# Fake6509_v2.net
KiCad netlist of a schematic drawn in EAGLE
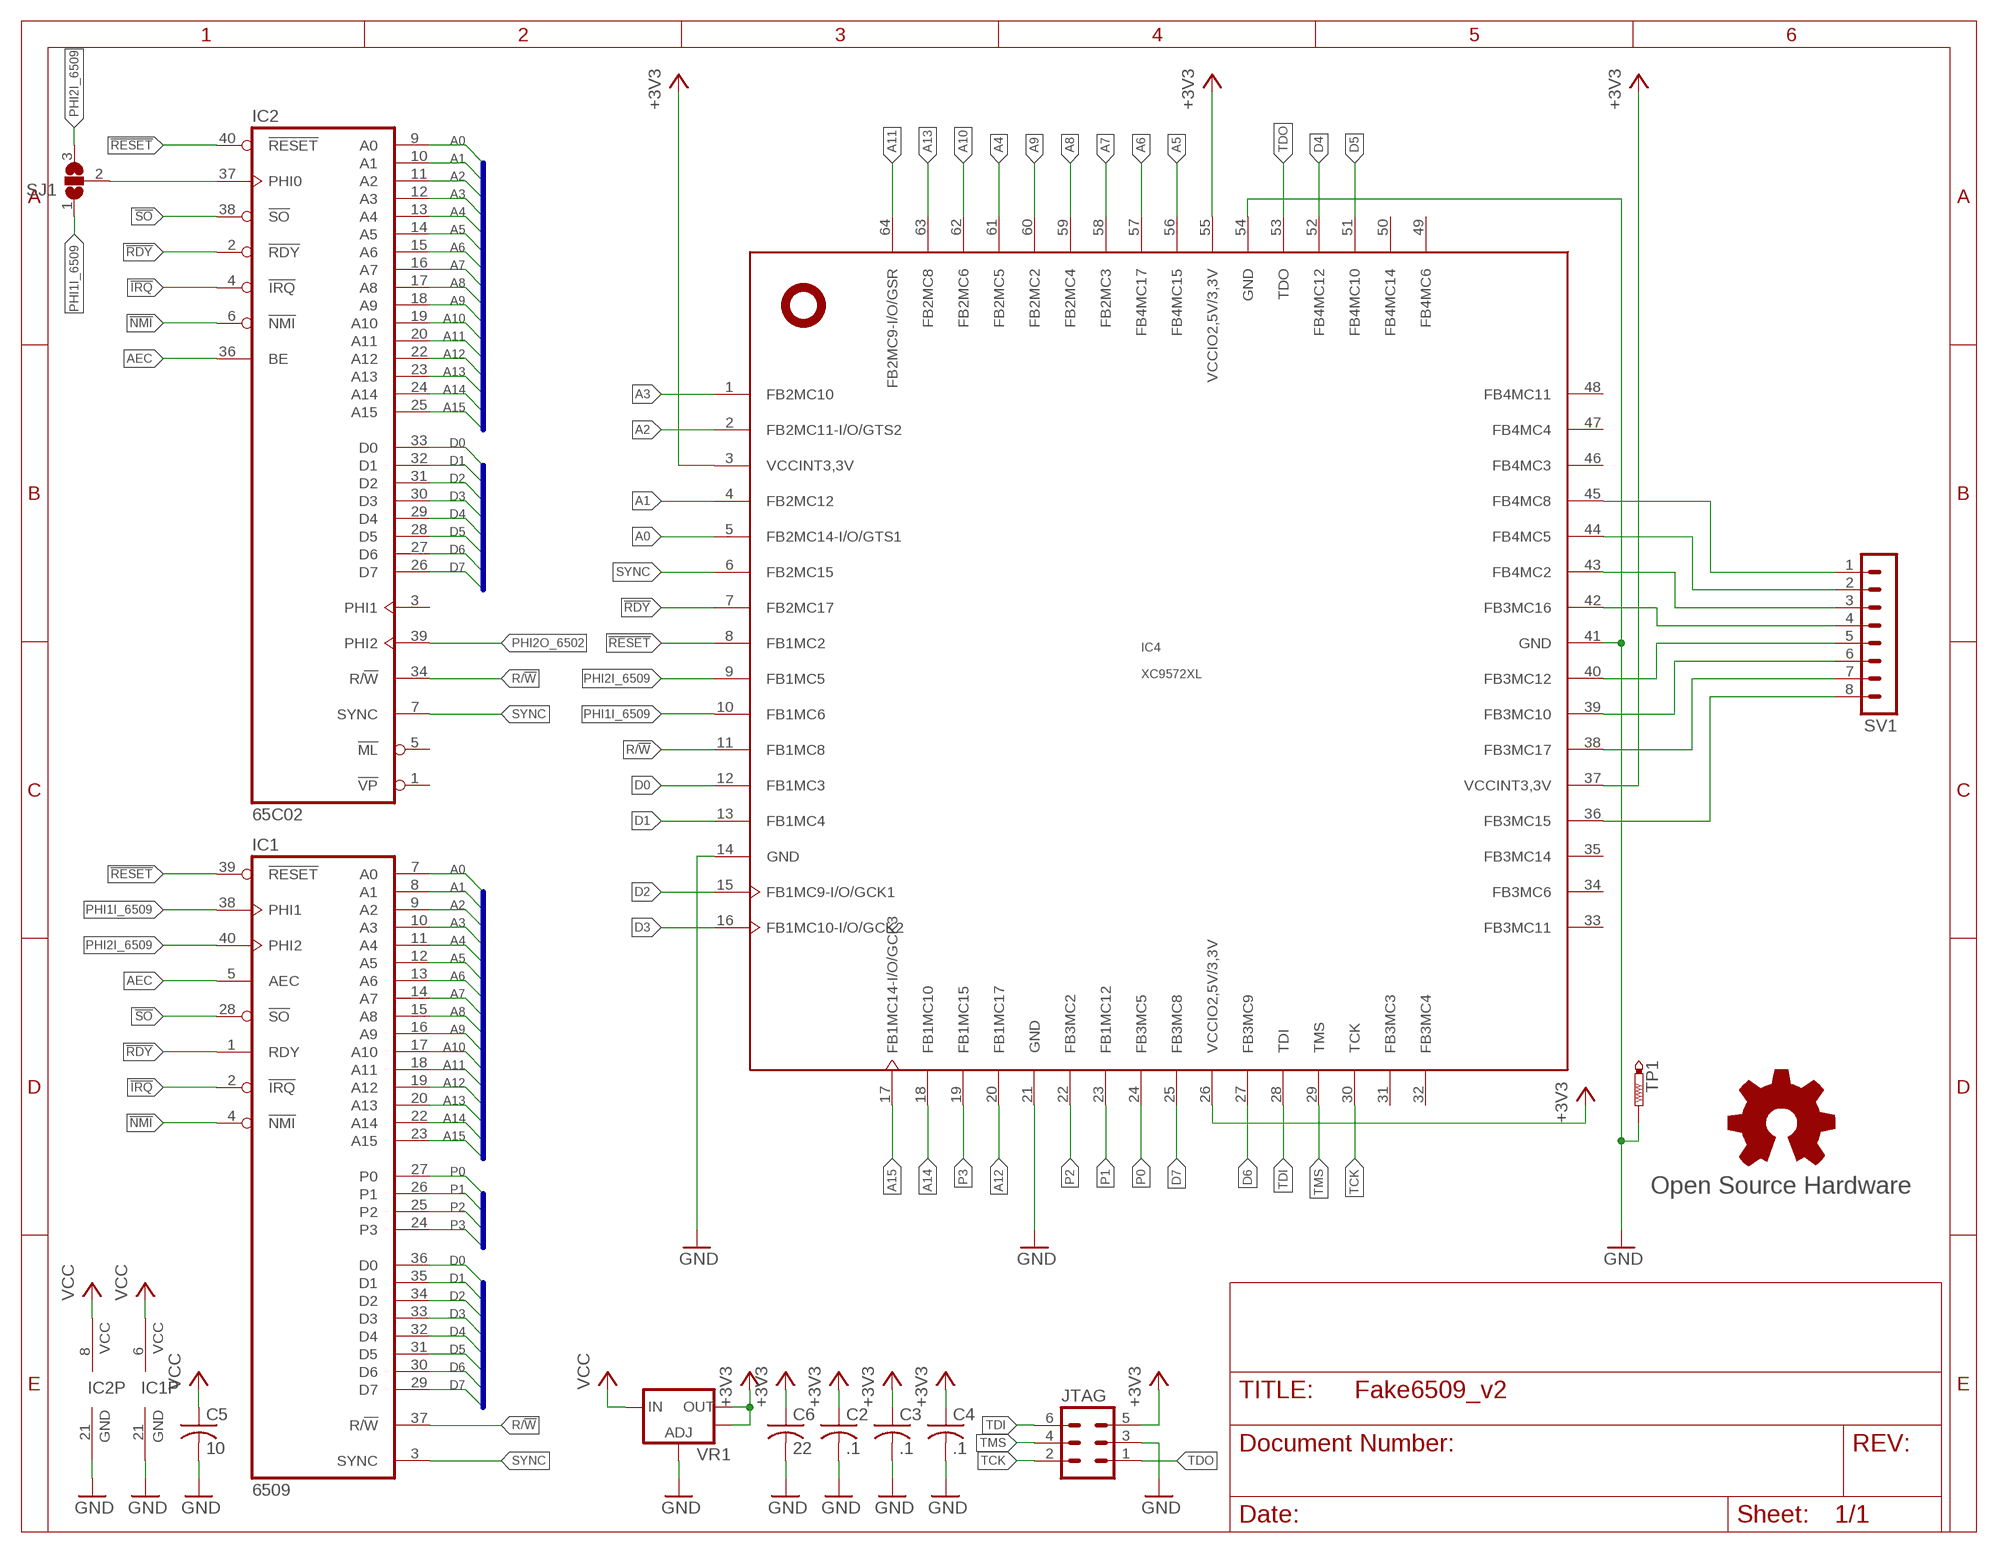
[diagram p0: schematic, sheet 1]

(export (version "E")
  (design (tool "Eeschema 10.0.6"))
  (components
    (comp (ref "C2")
      (value ".1")
      (footprint "eagle-import:C0402")
      (libsource (lib "eagle-import") (part "C-USC0402"))
    )
    (comp (ref "C3")
      (value ".1")
      (footprint "eagle-import:C0402")
      (libsource (lib "eagle-import") (part "C-USC0402"))
    )
    (comp (ref "C4")
      (value ".1")
      (footprint "eagle-import:C0402")
      (libsource (lib "eagle-import") (part "C-USC0402"))
    )
    (comp (ref "C5")
      (value "10")
      (footprint "eagle-import:C0805")
      (libsource (lib "eagle-import") (part "C-USC0805"))
    )
    (comp (ref "C6")
      (value "22")
      (footprint "eagle-import:C0805")
      (libsource (lib "eagle-import") (part "C-USC0805"))
    )
    (comp (ref "GOLD_ORB_SM1")
      (value "Open Source Hardware")
      (footprint "eagle-import:OSHW_5MM")
      (libsource (lib "eagle-import") (part "OSHWLOGOLOGO5MM"))
    )
    (comp (ref "IC1")
      (value "6509")
      (footprint "eagle-import:DIL40-ROUNDPAD")
      (libsource (lib "eagle-import") (part "6509-RP"))
    )
    (comp (ref "IC2")
      (value "65C02")
      (footprint "eagle-import:DIL40-ROUNDPAD")
      (libsource (lib "eagle-import") (part "W65C02SP-R"))
    )
    (comp (ref "IC4")
      (value "XC9572XL")
      (footprint "eagle-import:VQFP64")
      (libsource (lib "eagle-import") (part "XC9572XLVQG64"))
    )
    (comp (ref "JTAG")
      (value "MA03-2")
      (footprint "eagle-import:MA03-2")
      (libsource (lib "eagle-import") (part "MA03-2"))
    )
    (comp (ref "SJ1")
      (value "SJ2W")
      (footprint "eagle-import:SJ_2")
      (libsource (lib "eagle-import") (part "SJ2W"))
    )
    (comp (ref "SV1")
      (value "MA08-1")
      (footprint "eagle-import:MA08-1")
      (libsource (lib "eagle-import") (part "MA08-1"))
    )
    (comp (ref "TP1")
      (value "PTR1B1,27")
      (footprint "eagle-import:B1,27")
      (libsource (lib "eagle-import") (part "PTR1B1,27"))
    )
    (comp (ref "VR1")
      (value "V_REG_LM1117SOT223")
      (footprint "eagle-import:SOT223")
      (libsource (lib "eagle-import") (part "V_REG_LM1117SOT223"))
    )
  )
  (nets
    (net (code "1") (name "+3V3") (class "Default")
      (node (ref "C2") (pin "1") (pinfunction "1_1") (pintype "passive"))
      (node (ref "C3") (pin "1") (pinfunction "1_1") (pintype "passive"))
      (node (ref "C4") (pin "1") (pinfunction "1_1") (pintype "passive"))
      (node (ref "C6") (pin "1") (pinfunction "1_1") (pintype "passive"))
      (node (ref "IC4") (pin "26") (pinfunction "VCCIO2,5V/3,3V_26") (pintype "power_in"))
      (node (ref "IC4") (pin "3") (pinfunction "VCCINT3,3V_3") (pintype "power_in"))
      (node (ref "IC4") (pin "37") (pinfunction "VCCINT3,3V_37") (pintype "power_in"))
      (node (ref "IC4") (pin "55") (pinfunction "VCCIO2,5V/3,3V_55") (pintype "power_in"))
      (node (ref "JTAG") (pin "5") (pinfunction "5_5") (pintype "passive"))
      (node (ref "VR1") (pin "2") (pinfunction "OUT_2") (pintype "output"))
      (node (ref "VR1") (pin "4") (pinfunction "OUT_4") (pintype "output"))
    )
    (net (code "2") (name "/R{slash}~{W}") (class "Default")
      (node (ref "IC1") (pin "37") (pinfunction "R/~{W}_37") (pintype "output"))
      (node (ref "IC2") (pin "34") (pinfunction "R/~{W}_34") (pintype "output"))
      (node (ref "IC4") (pin "11") (pinfunction "FB1MC8_11") (pintype "bidirectional"))
    )
    (net (code "3") (name "/~{IRQ}") (class "Default")
      (node (ref "IC1") (pin "2") (pinfunction "~{IRQ}_2") (pintype "input"))
      (node (ref "IC2") (pin "4") (pinfunction "~{IRQ}_4") (pintype "input"))
    )
    (net (code "4") (name "/~{NMI}") (class "Default")
      (node (ref "IC1") (pin "4") (pinfunction "~{NMI}_4") (pintype "input"))
      (node (ref "IC2") (pin "6") (pinfunction "~{NMI}_6") (pintype "input"))
    )
    (net (code "5") (name "/~{RDY}") (class "Default")
      (node (ref "IC1") (pin "1") (pinfunction "RDY_1") (pintype "input"))
      (node (ref "IC2") (pin "2") (pinfunction "~{RDY}_2") (pintype "bidirectional"))
      (node (ref "IC4") (pin "7") (pinfunction "FB2MC17_7") (pintype "bidirectional"))
    )
    (net (code "6") (name "/~{RESET}") (class "Default")
      (node (ref "IC1") (pin "39") (pinfunction "~{RESET}_39") (pintype "input"))
      (node (ref "IC2") (pin "40") (pinfunction "~{RESET}_40") (pintype "input"))
      (node (ref "IC4") (pin "8") (pinfunction "FB1MC2_8") (pintype "bidirectional"))
    )
    (net (code "7") (name "/~{SO}") (class "Default")
      (node (ref "IC1") (pin "28") (pinfunction "~{SO}_28") (pintype "input"))
      (node (ref "IC2") (pin "38") (pinfunction "~{SO}_38") (pintype "input"))
    )
    (net (code "8") (name "A0") (class "Default")
      (node (ref "IC1") (pin "7") (pinfunction "A0_7") (pintype "output"))
      (node (ref "IC2") (pin "9") (pinfunction "A0_9") (pintype "bidirectional"))
      (node (ref "IC4") (pin "5") (pinfunction "FB2MC14-I/O/GTS1_5") (pintype "bidirectional"))
    )
    (net (code "9") (name "A1") (class "Default")
      (node (ref "IC1") (pin "8") (pinfunction "A1_8") (pintype "output"))
      (node (ref "IC2") (pin "10") (pinfunction "A1_10") (pintype "bidirectional"))
      (node (ref "IC4") (pin "4") (pinfunction "FB2MC12_4") (pintype "bidirectional"))
    )
    (net (code "10") (name "A2") (class "Default")
      (node (ref "IC1") (pin "9") (pinfunction "A2_9") (pintype "output"))
      (node (ref "IC2") (pin "11") (pinfunction "A2_11") (pintype "bidirectional"))
      (node (ref "IC4") (pin "2") (pinfunction "FB2MC11-I/O/GTS2_2") (pintype "bidirectional"))
    )
    (net (code "11") (name "A3") (class "Default")
      (node (ref "IC1") (pin "10") (pinfunction "A3_10") (pintype "output"))
      (node (ref "IC2") (pin "12") (pinfunction "A3_12") (pintype "bidirectional"))
      (node (ref "IC4") (pin "1") (pinfunction "FB2MC10_1") (pintype "bidirectional"))
    )
    (net (code "12") (name "A4") (class "Default")
      (node (ref "IC1") (pin "11") (pinfunction "A4_11") (pintype "output"))
      (node (ref "IC2") (pin "13") (pinfunction "A4_13") (pintype "bidirectional"))
      (node (ref "IC4") (pin "61") (pinfunction "FB2MC5_61") (pintype "bidirectional"))
    )
    (net (code "13") (name "A5") (class "Default")
      (node (ref "IC1") (pin "12") (pinfunction "A5_12") (pintype "output"))
      (node (ref "IC2") (pin "14") (pinfunction "A5_14") (pintype "bidirectional"))
      (node (ref "IC4") (pin "56") (pinfunction "FB4MC15_56") (pintype "bidirectional"))
    )
    (net (code "14") (name "A6") (class "Default")
      (node (ref "IC1") (pin "13") (pinfunction "A6_13") (pintype "output"))
      (node (ref "IC2") (pin "15") (pinfunction "A6_15") (pintype "bidirectional"))
      (node (ref "IC4") (pin "57") (pinfunction "FB4MC17_57") (pintype "bidirectional"))
    )
    (net (code "15") (name "A7") (class "Default")
      (node (ref "IC1") (pin "14") (pinfunction "A7_14") (pintype "output"))
      (node (ref "IC2") (pin "16") (pinfunction "A7_16") (pintype "bidirectional"))
      (node (ref "IC4") (pin "58") (pinfunction "FB2MC3_58") (pintype "bidirectional"))
    )
    (net (code "16") (name "A8") (class "Default")
      (node (ref "IC1") (pin "15") (pinfunction "A8_15") (pintype "output"))
      (node (ref "IC2") (pin "17") (pinfunction "A8_17") (pintype "bidirectional"))
      (node (ref "IC4") (pin "59") (pinfunction "FB2MC4_59") (pintype "bidirectional"))
    )
    (net (code "17") (name "A9") (class "Default")
      (node (ref "IC1") (pin "16") (pinfunction "A9_16") (pintype "output"))
      (node (ref "IC2") (pin "18") (pinfunction "A9_18") (pintype "bidirectional"))
      (node (ref "IC4") (pin "60") (pinfunction "FB2MC2_60") (pintype "bidirectional"))
    )
    (net (code "18") (name "A10") (class "Default")
      (node (ref "IC1") (pin "17") (pinfunction "A10_17") (pintype "output"))
      (node (ref "IC2") (pin "19") (pinfunction "A10_19") (pintype "bidirectional"))
      (node (ref "IC4") (pin "62") (pinfunction "FB2MC6_62") (pintype "bidirectional"))
    )
    (net (code "19") (name "A11") (class "Default")
      (node (ref "IC1") (pin "18") (pinfunction "A11_18") (pintype "output"))
      (node (ref "IC2") (pin "20") (pinfunction "A11_20") (pintype "bidirectional"))
      (node (ref "IC4") (pin "64") (pinfunction "FB2MC9-I/O/GSR_64") (pintype "bidirectional"))
    )
    (net (code "20") (name "A12") (class "Default")
      (node (ref "IC1") (pin "19") (pinfunction "A12_19") (pintype "output"))
      (node (ref "IC2") (pin "22") (pinfunction "A12_22") (pintype "bidirectional"))
      (node (ref "IC4") (pin "20") (pinfunction "FB1MC17_20") (pintype "bidirectional"))
    )
    (net (code "21") (name "A13") (class "Default")
      (node (ref "IC1") (pin "20") (pinfunction "A13_20") (pintype "output"))
      (node (ref "IC2") (pin "23") (pinfunction "A13_23") (pintype "bidirectional"))
      (node (ref "IC4") (pin "63") (pinfunction "FB2MC8_63") (pintype "bidirectional"))
    )
    (net (code "22") (name "A14") (class "Default")
      (node (ref "IC1") (pin "22") (pinfunction "A14_22") (pintype "output"))
      (node (ref "IC2") (pin "24") (pinfunction "A14_24") (pintype "bidirectional"))
      (node (ref "IC4") (pin "18") (pinfunction "FB1MC10_18") (pintype "bidirectional"))
    )
    (net (code "23") (name "A15") (class "Default")
      (node (ref "IC1") (pin "23") (pinfunction "A15_23") (pintype "output"))
      (node (ref "IC2") (pin "25") (pinfunction "A15_25") (pintype "bidirectional"))
      (node (ref "IC4") (pin "17") (pinfunction "FB1MC14-I/O/GCK3_17") (pintype "bidirectional"))
    )
    (net (code "24") (name "AEC") (class "Default")
      (node (ref "IC1") (pin "5") (pinfunction "AEC_5") (pintype "input"))
      (node (ref "IC2") (pin "36") (pinfunction "BE_36") (pintype "input"))
    )
    (net (code "25") (name "D0") (class "Default")
      (node (ref "IC1") (pin "36") (pinfunction "D0_36") (pintype "bidirectional"))
      (node (ref "IC2") (pin "33") (pinfunction "D0_33") (pintype "bidirectional"))
      (node (ref "IC4") (pin "12") (pinfunction "FB1MC3_12") (pintype "bidirectional"))
    )
    (net (code "26") (name "D1") (class "Default")
      (node (ref "IC1") (pin "35") (pinfunction "D1_35") (pintype "bidirectional"))
      (node (ref "IC2") (pin "32") (pinfunction "D1_32") (pintype "bidirectional"))
      (node (ref "IC4") (pin "13") (pinfunction "FB1MC4_13") (pintype "bidirectional"))
    )
    (net (code "27") (name "D2") (class "Default")
      (node (ref "IC1") (pin "34") (pinfunction "D2_34") (pintype "bidirectional"))
      (node (ref "IC2") (pin "31") (pinfunction "D2_31") (pintype "bidirectional"))
      (node (ref "IC4") (pin "15") (pinfunction "FB1MC9-I/O/GCK1_15") (pintype "bidirectional"))
    )
    (net (code "28") (name "D3") (class "Default")
      (node (ref "IC1") (pin "33") (pinfunction "D3_33") (pintype "bidirectional"))
      (node (ref "IC2") (pin "30") (pinfunction "D3_30") (pintype "bidirectional"))
      (node (ref "IC4") (pin "16") (pinfunction "FB1MC10-I/O/GCK2_16") (pintype "bidirectional"))
    )
    (net (code "29") (name "D4") (class "Default")
      (node (ref "IC1") (pin "32") (pinfunction "D4_32") (pintype "bidirectional"))
      (node (ref "IC2") (pin "29") (pinfunction "D4_29") (pintype "bidirectional"))
      (node (ref "IC4") (pin "52") (pinfunction "FB4MC12_52") (pintype "bidirectional"))
    )
    (net (code "30") (name "D5") (class "Default")
      (node (ref "IC1") (pin "31") (pinfunction "D5_31") (pintype "bidirectional"))
      (node (ref "IC2") (pin "28") (pinfunction "D5_28") (pintype "bidirectional"))
      (node (ref "IC4") (pin "51") (pinfunction "FB4MC10_51") (pintype "bidirectional"))
    )
    (net (code "31") (name "D6") (class "Default")
      (node (ref "IC1") (pin "30") (pinfunction "D6_30") (pintype "bidirectional"))
      (node (ref "IC2") (pin "27") (pinfunction "D6_27") (pintype "bidirectional"))
      (node (ref "IC4") (pin "27") (pinfunction "FB3MC9_27") (pintype "bidirectional"))
    )
    (net (code "32") (name "D7") (class "Default")
      (node (ref "IC1") (pin "29") (pinfunction "D7_29") (pintype "bidirectional"))
      (node (ref "IC2") (pin "26") (pinfunction "D7_26") (pintype "bidirectional"))
      (node (ref "IC4") (pin "25") (pinfunction "FB3MC8_25") (pintype "bidirectional"))
    )
    (net (code "33") (name "GND") (class "Default")
      (node (ref "C2") (pin "2") (pinfunction "2_2") (pintype "passive"))
      (node (ref "C3") (pin "2") (pinfunction "2_2") (pintype "passive"))
      (node (ref "C4") (pin "2") (pinfunction "2_2") (pintype "passive"))
      (node (ref "C5") (pin "2") (pinfunction "2_2") (pintype "passive"))
      (node (ref "C6") (pin "2") (pinfunction "2_2") (pintype "passive"))
      (node (ref "IC1") (pin "21") (pinfunction "GND_21") (pintype "power_in"))
      (node (ref "IC2") (pin "21") (pinfunction "GND_21") (pintype "power_in"))
      (node (ref "IC4") (pin "14") (pinfunction "GND_14") (pintype "power_in"))
      (node (ref "IC4") (pin "21") (pinfunction "GND_21") (pintype "power_in"))
      (node (ref "IC4") (pin "41") (pinfunction "GND_41") (pintype "power_in"))
      (node (ref "IC4") (pin "54") (pinfunction "GND_54") (pintype "power_in"))
      (node (ref "JTAG") (pin "3") (pinfunction "3_3") (pintype "passive"))
      (node (ref "TP1") (pin "TP") (pinfunction "TP_TP") (pintype "input"))
      (node (ref "VR1") (pin "1") (pinfunction "ADJ_1") (pintype "input"))
    )
    (net (code "34") (name "Net-(IC2A-PHI0)") (class "Default")
      (node (ref "IC2") (pin "37") (pinfunction "PHI0_37") (pintype "input"))
      (node (ref "SJ1") (pin "2") (pinfunction "2_2") (pintype "passive"))
    )
    (net (code "35") (name "Net-(IC4-FB3MC10)") (class "Default")
      (node (ref "IC4") (pin "39") (pinfunction "FB3MC10_39") (pintype "bidirectional"))
      (node (ref "SV1") (pin "6") (pinfunction "6_6") (pintype "passive"))
    )
    (net (code "36") (name "Net-(IC4-FB3MC12)") (class "Default")
      (node (ref "IC4") (pin "40") (pinfunction "FB3MC12_40") (pintype "bidirectional"))
      (node (ref "SV1") (pin "5") (pinfunction "5_5") (pintype "passive"))
    )
    (net (code "37") (name "Net-(IC4-FB3MC15)") (class "Default")
      (node (ref "IC4") (pin "36") (pinfunction "FB3MC15_36") (pintype "bidirectional"))
      (node (ref "SV1") (pin "8") (pinfunction "8_8") (pintype "passive"))
    )
    (net (code "38") (name "Net-(IC4-FB3MC16)") (class "Default")
      (node (ref "IC4") (pin "42") (pinfunction "FB3MC16_42") (pintype "bidirectional"))
      (node (ref "SV1") (pin "4") (pinfunction "4_4") (pintype "passive"))
    )
    (net (code "39") (name "Net-(IC4-FB3MC17)") (class "Default")
      (node (ref "IC4") (pin "38") (pinfunction "FB3MC17_38") (pintype "bidirectional"))
      (node (ref "SV1") (pin "7") (pinfunction "7_7") (pintype "passive"))
    )
    (net (code "40") (name "Net-(IC4-FB4MC2)") (class "Default")
      (node (ref "IC4") (pin "43") (pinfunction "FB4MC2_43") (pintype "bidirectional"))
      (node (ref "SV1") (pin "3") (pinfunction "3_3") (pintype "passive"))
    )
    (net (code "41") (name "Net-(IC4-FB4MC5)") (class "Default")
      (node (ref "IC4") (pin "44") (pinfunction "FB4MC5_44") (pintype "bidirectional"))
      (node (ref "SV1") (pin "2") (pinfunction "2_2") (pintype "passive"))
    )
    (net (code "42") (name "Net-(IC4-FB4MC8)") (class "Default")
      (node (ref "IC4") (pin "45") (pinfunction "FB4MC8_45") (pintype "bidirectional"))
      (node (ref "SV1") (pin "1") (pinfunction "1_1") (pintype "passive"))
    )
    (net (code "43") (name "P0") (class "Default")
      (node (ref "IC1") (pin "27") (pinfunction "P0_27") (pintype "output"))
      (node (ref "IC4") (pin "24") (pinfunction "FB3MC5_24") (pintype "bidirectional"))
    )
    (net (code "44") (name "P1") (class "Default")
      (node (ref "IC1") (pin "26") (pinfunction "P1_26") (pintype "output"))
      (node (ref "IC4") (pin "23") (pinfunction "FB1MC12_23") (pintype "bidirectional"))
    )
    (net (code "45") (name "P2") (class "Default")
      (node (ref "IC1") (pin "25") (pinfunction "P2_25") (pintype "output"))
      (node (ref "IC4") (pin "22") (pinfunction "FB3MC2_22") (pintype "bidirectional"))
    )
    (net (code "46") (name "P3") (class "Default")
      (node (ref "IC1") (pin "24") (pinfunction "P3_24") (pintype "output"))
      (node (ref "IC4") (pin "19") (pinfunction "FB1MC15_19") (pintype "bidirectional"))
    )
    (net (code "47") (name "PHI1I_6509") (class "Default")
      (node (ref "IC1") (pin "38") (pinfunction "PHI1_38") (pintype "input"))
      (node (ref "IC4") (pin "10") (pinfunction "FB1MC6_10") (pintype "bidirectional"))
      (node (ref "SJ1") (pin "1") (pinfunction "1_1") (pintype "passive"))
    )
    (net (code "48") (name "PHI2I_6509") (class "Default")
      (node (ref "IC1") (pin "40") (pinfunction "PHI2_40") (pintype "input"))
      (node (ref "IC4") (pin "9") (pinfunction "FB1MC5_9") (pintype "bidirectional"))
      (node (ref "SJ1") (pin "3") (pinfunction "3_3") (pintype "passive"))
    )
    (net (code "49") (name "PHI2O_6502") (class "Default")
      (node (ref "IC2") (pin "39") (pinfunction "PHI2_39") (pintype "output"))
    )
    (net (code "50") (name "SYNC") (class "Default")
      (node (ref "IC1") (pin "3") (pinfunction "SYNC_3") (pintype "output"))
      (node (ref "IC2") (pin "7") (pinfunction "SYNC_7") (pintype "output"))
      (node (ref "IC4") (pin "6") (pinfunction "FB2MC15_6") (pintype "bidirectional"))
    )
    (net (code "51") (name "TCK") (class "Default")
      (node (ref "IC4") (pin "30") (pinfunction "TCK_30") (pintype "bidirectional"))
      (node (ref "JTAG") (pin "2") (pinfunction "2_2") (pintype "passive"))
    )
    (net (code "52") (name "TDI") (class "Default")
      (node (ref "IC4") (pin "28") (pinfunction "TDI_28") (pintype "bidirectional"))
      (node (ref "JTAG") (pin "6") (pinfunction "6_6") (pintype "passive"))
    )
    (net (code "53") (name "TDO") (class "Default")
      (node (ref "IC4") (pin "53") (pinfunction "TDO_53") (pintype "bidirectional"))
      (node (ref "JTAG") (pin "1") (pinfunction "1_1") (pintype "passive"))
    )
    (net (code "54") (name "TMS") (class "Default")
      (node (ref "IC4") (pin "29") (pinfunction "TMS_29") (pintype "bidirectional"))
      (node (ref "JTAG") (pin "4") (pinfunction "4_4") (pintype "passive"))
    )
    (net (code "55") (name "VCC") (class "Default")
      (node (ref "C5") (pin "1") (pinfunction "1_1") (pintype "passive"))
      (node (ref "IC1") (pin "6") (pinfunction "VCC_6") (pintype "power_in"))
      (node (ref "IC2") (pin "8") (pinfunction "VCC_8") (pintype "power_in"))
      (node (ref "VR1") (pin "3") (pinfunction "IN_3") (pintype "input"))
    )
    (net (code "56") (name "unconnected-(IC2A-PHI1-Pad3)") (class "Default")
      (node (ref "IC2") (pin "3") (pinfunction "PHI1_3") (pintype "output"))
    )
    (net (code "57") (name "unconnected-(IC2A-~{ML}-Pad5)") (class "Default")
      (node (ref "IC2") (pin "5") (pinfunction "~{ML}_5") (pintype "output"))
    )
    (net (code "58") (name "unconnected-(IC2A-~{VP}-Pad1)") (class "Default")
      (node (ref "IC2") (pin "1") (pinfunction "~{VP}_1") (pintype "output"))
    )
    (net (code "59") (name "unconnected-(IC4-FB3MC3-Pad31)") (class "Default")
      (node (ref "IC4") (pin "31") (pinfunction "FB3MC3_31") (pintype "bidirectional"))
    )
    (net (code "60") (name "unconnected-(IC4-FB3MC4-Pad32)") (class "Default")
      (node (ref "IC4") (pin "32") (pinfunction "FB3MC4_32") (pintype "bidirectional"))
    )
    (net (code "61") (name "unconnected-(IC4-FB3MC6-Pad34)") (class "Default")
      (node (ref "IC4") (pin "34") (pinfunction "FB3MC6_34") (pintype "bidirectional"))
    )
    (net (code "62") (name "unconnected-(IC4-FB3MC11-Pad33)") (class "Default")
      (node (ref "IC4") (pin "33") (pinfunction "FB3MC11_33") (pintype "bidirectional"))
    )
    (net (code "63") (name "unconnected-(IC4-FB3MC14-Pad35)") (class "Default")
      (node (ref "IC4") (pin "35") (pinfunction "FB3MC14_35") (pintype "bidirectional"))
    )
    (net (code "64") (name "unconnected-(IC4-FB4MC3-Pad46)") (class "Default")
      (node (ref "IC4") (pin "46") (pinfunction "FB4MC3_46") (pintype "bidirectional"))
    )
    (net (code "65") (name "unconnected-(IC4-FB4MC4-Pad47)") (class "Default")
      (node (ref "IC4") (pin "47") (pinfunction "FB4MC4_47") (pintype "bidirectional"))
    )
    (net (code "66") (name "unconnected-(IC4-FB4MC6-Pad49)") (class "Default")
      (node (ref "IC4") (pin "49") (pinfunction "FB4MC6_49") (pintype "bidirectional"))
    )
    (net (code "67") (name "unconnected-(IC4-FB4MC11-Pad48)") (class "Default")
      (node (ref "IC4") (pin "48") (pinfunction "FB4MC11_48") (pintype "bidirectional"))
    )
    (net (code "68") (name "unconnected-(IC4-FB4MC14-Pad50)") (class "Default")
      (node (ref "IC4") (pin "50") (pinfunction "FB4MC14_50") (pintype "bidirectional"))
    )
  )
)
